# TangPrimer_no_jtag.net
KiCad netlist of a schematic drawn in EAGLE
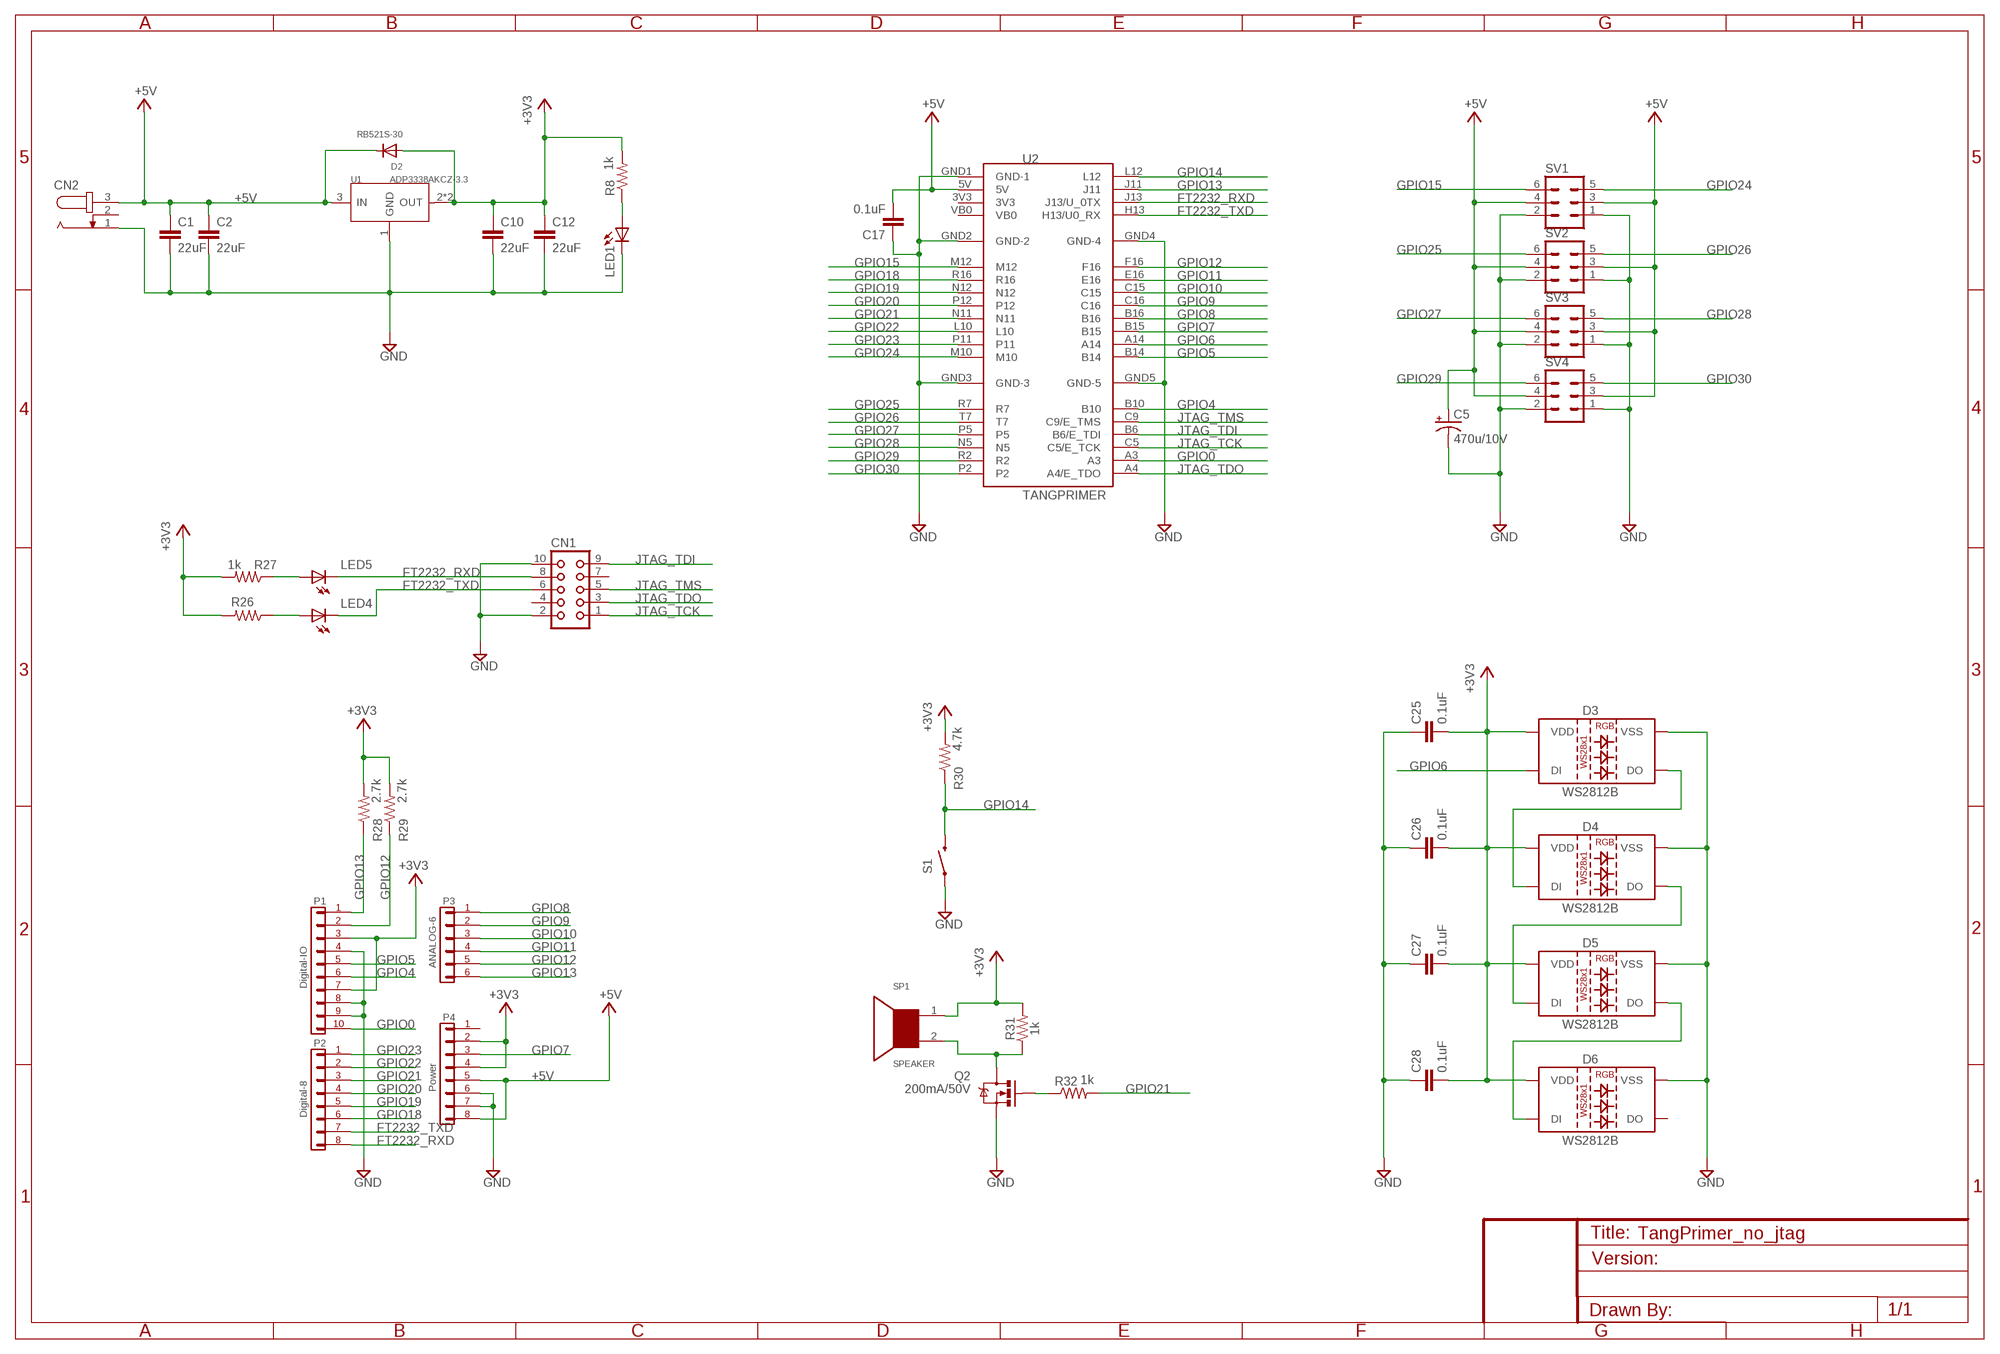
[diagram p0: schematic, sheet 1]

(export (version "E")
  (design (tool "Eeschema 10.0.6"))
  (components
    (comp (ref "C1")
      (value "22uF")
      (footprint "eagle-import:0603")
      (libsource (lib "eagle-import") (part "10UF-0603-6.3V-20%"))
    )
    (comp (ref "C2")
      (value "22uF")
      (footprint "eagle-import:0603")
      (libsource (lib "eagle-import") (part "10UF-0603-6.3V-20%"))
    )
    (comp (ref "C5")
      (value "470u/10V")
      (footprint "eagle-import:E2,5-7")
      (libsource (lib "eagle-import") (part "CPOL-USE2.5-7"))
    )
    (comp (ref "C10")
      (value "22uF")
      (footprint "eagle-import:0603")
      (libsource (lib "eagle-import") (part "10UF-0603-6.3V-20%"))
    )
    (comp (ref "C12")
      (value "22uF")
      (footprint "eagle-import:0603")
      (libsource (lib "eagle-import") (part "10UF-0603-6.3V-20%"))
    )
    (comp (ref "C17")
      (value "0.1uF")
      (footprint "eagle-import:0603")
      (libsource (lib "eagle-import") (part "0.1UF-0603-25V-5%"))
    )
    (comp (ref "C25")
      (value "0.1uF")
      (footprint "eagle-import:0603")
      (libsource (lib "eagle-import") (part "0.1UF-0603-25V-5%"))
    )
    (comp (ref "C26")
      (value "0.1uF")
      (footprint "eagle-import:0603")
      (libsource (lib "eagle-import") (part "0.1UF-0603-25V-5%"))
    )
    (comp (ref "C27")
      (value "0.1uF")
      (footprint "eagle-import:0603")
      (libsource (lib "eagle-import") (part "0.1UF-0603-25V-5%"))
    )
    (comp (ref "C28")
      (value "0.1uF")
      (footprint "eagle-import:0603")
      (libsource (lib "eagle-import") (part "0.1UF-0603-25V-5%"))
    )
    (comp (ref "CN1")
      (value "CON10")
      (footprint "eagle-import:CON10")
      (libsource (lib "eagle-import") (part "CON10"))
    )
    (comp (ref "CN2")
      (value "JACK-PLUG0")
      (footprint "eagle-import:SPC4077")
      (libsource (lib "eagle-import") (part "JACK-PLUG0"))
    )
    (comp (ref "D2")
      (value "RB521S-30")
      (footprint "eagle-import:SOD-523")
      (libsource (lib "eagle-import") (part "DIODESOD-523"))
    )
    (comp (ref "D3")
      (value "WS2812B")
      (footprint "eagle-import:WS2812_2020")
      (libsource (lib "eagle-import") (part "WS2812_2020"))
    )
    (comp (ref "D4")
      (value "WS2812B")
      (footprint "eagle-import:WS2812_2020")
      (libsource (lib "eagle-import") (part "WS2812_2020"))
    )
    (comp (ref "D5")
      (value "WS2812B")
      (footprint "eagle-import:WS2812_2020")
      (libsource (lib "eagle-import") (part "WS2812_2020"))
    )
    (comp (ref "D6")
      (value "WS2812B")
      (footprint "eagle-import:WS2812_2020")
      (libsource (lib "eagle-import") (part "WS2812_2020"))
    )
    (comp (ref "LED1")
      (value "LEDCHIP-LED0805")
      (footprint "eagle-import:CHIP-LED0805")
      (libsource (lib "eagle-import") (part "LEDCHIP-LED0805"))
    )
    (comp (ref "LED4")
      (value "LEDCHIP-LED0805")
      (footprint "eagle-import:CHIP-LED0805")
      (libsource (lib "eagle-import") (part "LEDCHIP-LED0805"))
    )
    (comp (ref "LED5")
      (value "LEDCHIP-LED0805")
      (footprint "eagle-import:CHIP-LED0805")
      (libsource (lib "eagle-import") (part "LEDCHIP-LED0805"))
    )
    (comp (ref "Q2")
      (value "200mA/50V")
      (footprint "eagle-import:SOT23-3")
      (libsource (lib "eagle-import") (part "MOSFET-NCHANNELBSS138"))
    )
    (comp (ref "R8")
      (value "1k")
      (footprint "eagle-import:0603")
      (libsource (lib "eagle-import") (part "RESISTOR0603"))
    )
    (comp (ref "R26")
      (value "1k")
      (footprint "eagle-import:0603")
      (libsource (lib "eagle-import") (part "RESISTOR0603"))
    )
    (comp (ref "R27")
      (value "1k")
      (footprint "eagle-import:0603")
      (libsource (lib "eagle-import") (part "RESISTOR0603"))
    )
    (comp (ref "R28")
      (value "2.7k")
      (footprint "eagle-import:0603")
      (libsource (lib "eagle-import") (part "RESISTOR0603"))
    )
    (comp (ref "R29")
      (value "2.7k")
      (footprint "eagle-import:0603")
      (libsource (lib "eagle-import") (part "RESISTOR0603"))
    )
    (comp (ref "R30")
      (value "4.7k")
      (footprint "eagle-import:0603")
      (libsource (lib "eagle-import") (part "RESISTOR0603"))
    )
    (comp (ref "R31")
      (value "1k")
      (footprint "eagle-import:0603")
      (libsource (lib "eagle-import") (part "RESISTOR0603"))
    )
    (comp (ref "R32")
      (value "1k")
      (footprint "eagle-import:0603")
      (libsource (lib "eagle-import") (part "RESISTOR0603"))
    )
    (comp (ref "S1")
      (value "SWITCH-MOMENTARY-2SMD-1101NE")
      (footprint "eagle-import:TACTILE-SWITCH-1101NE")
      (libsource (lib "eagle-import") (part "SWITCH-MOMENTARY-2SMD-1101NE"))
    )
    (comp (ref "S2")
      (value "TANGPRIMER_BASE")
      (footprint "eagle-import:TANGPRIMER_BASE")
      (libsource (lib "eagle-import") (part "TANGPRIMER_BASE"))
    )
    (comp (ref "SP1")
      (value "SPEAKER")
      (footprint "eagle-import:SPEAKER")
      (libsource (lib "eagle-import") (part "SPEAKER"))
    )
    (comp (ref "SV1")
      (value "MA03-2")
      (footprint "eagle-import:MA03-2")
      (libsource (lib "eagle-import") (part "MA03-2"))
    )
    (comp (ref "SV2")
      (value "MA03-2")
      (footprint "eagle-import:MA03-2")
      (libsource (lib "eagle-import") (part "MA03-2"))
    )
    (comp (ref "SV3")
      (value "MA03-2")
      (footprint "eagle-import:MA03-2")
      (libsource (lib "eagle-import") (part "MA03-2"))
    )
    (comp (ref "SV4")
      (value "MA03-2")
      (footprint "eagle-import:MA03-2")
      (libsource (lib "eagle-import") (part "MA03-2"))
    )
    (comp (ref "U1")
      (value "ADP3338AKCZ-3.3")
      (footprint "eagle-import:SOT-223")
      (fields (field (name "MPN") "CJT1117-3.3"))
      (libsource (lib "eagle-import") (part "PMIC-CJT1117-3.3(SOT223)"))
    )
    (comp (ref "U2")
      (value "TANGPRIMER")
      (footprint "eagle-import:TANGPRIMER")
      (libsource (lib "eagle-import") (part "TANGPRIMER"))
    )
  )
  (nets
    (net (code "1") (name "+3V3") (class "Default")
      (node (ref "C10") (pin "1") (pinfunction "1_1") (pintype "passive"))
      (node (ref "C12") (pin "1") (pinfunction "1_1") (pintype "passive"))
      (node (ref "C25") (pin "2") (pinfunction "2_2") (pintype "passive"))
      (node (ref "C26") (pin "2") (pinfunction "2_2") (pintype "passive"))
      (node (ref "C27") (pin "2") (pinfunction "2_2") (pintype "passive"))
      (node (ref "C28") (pin "2") (pinfunction "2_2") (pintype "passive"))
      (node (ref "D2") (pin "A") (pinfunction "A_A") (pintype "passive"))
      (node (ref "D3") (pin "4") (pinfunction "VDD_4") (pintype "bidirectional"))
      (node (ref "D4") (pin "4") (pinfunction "VDD_4") (pintype "bidirectional"))
      (node (ref "D5") (pin "4") (pinfunction "VDD_4") (pintype "bidirectional"))
      (node (ref "D6") (pin "4") (pinfunction "VDD_4") (pintype "bidirectional"))
      (node (ref "R26") (pin "2") (pinfunction "2_2") (pintype "passive"))
      (node (ref "R27") (pin "2") (pinfunction "2_2") (pintype "passive"))
      (node (ref "R28") (pin "2") (pinfunction "2_2") (pintype "passive"))
      (node (ref "R29") (pin "2") (pinfunction "2_2") (pintype "passive"))
      (node (ref "R30") (pin "2") (pinfunction "2_2") (pintype "passive"))
      (node (ref "R31") (pin "2") (pinfunction "2_2") (pintype "passive"))
      (node (ref "R8") (pin "2") (pinfunction "2_2") (pintype "passive"))
      (node (ref "S2") (pin "3V3-1") (pinfunction "3V3-1_3V3-1") (pintype "bidirectional"))
      (node (ref "S2") (pin "3V3-2") (pinfunction "3V3-2_3V3-2") (pintype "bidirectional"))
      (node (ref "S2") (pin "AREF") (pinfunction "AREF_AREF") (pintype "bidirectional"))
      (node (ref "S2") (pin "D11") (pinfunction "D11_D11") (pintype "bidirectional"))
      (node (ref "SP1") (pin "1") (pinfunction "1_1") (pintype "bidirectional"))
      (node (ref "U1") (pin "2") (pinfunction "OUT_2") (pintype "bidirectional"))
      (node (ref "U1") (pin "TER") (pinfunction "OUT_TER") (pintype "bidirectional"))
    )
    (net (code "2") (name "+5V") (class "Default")
      (node (ref "C1") (pin "1") (pinfunction "1_1") (pintype "passive"))
      (node (ref "C17") (pin "2") (pinfunction "2_2") (pintype "passive"))
      (node (ref "C2") (pin "1") (pinfunction "1_1") (pintype "passive"))
      (node (ref "C5") (pin "+") (pinfunction "+_+") (pintype "passive"))
      (node (ref "CN2") (pin "3") (pinfunction "3_3") (pintype "passive"))
      (node (ref "D2") (pin "K") (pinfunction "C_K") (pintype "passive"))
      (node (ref "S2") (pin "5V") (pinfunction "5V_5V") (pintype "bidirectional"))
      (node (ref "S2") (pin "VIN") (pinfunction "VIN_VIN") (pintype "bidirectional"))
      (node (ref "SV1") (pin "3") (pinfunction "3_3") (pintype "passive"))
      (node (ref "SV1") (pin "4") (pinfunction "4_4") (pintype "passive"))
      (node (ref "SV2") (pin "3") (pinfunction "3_3") (pintype "passive"))
      (node (ref "SV2") (pin "4") (pinfunction "4_4") (pintype "passive"))
      (node (ref "SV3") (pin "3") (pinfunction "3_3") (pintype "passive"))
      (node (ref "SV3") (pin "4") (pinfunction "4_4") (pintype "passive"))
      (node (ref "SV4") (pin "3") (pinfunction "3_3") (pintype "passive"))
      (node (ref "SV4") (pin "4") (pinfunction "4_4") (pintype "passive"))
      (node (ref "U1") (pin "3") (pinfunction "IN_3") (pintype "bidirectional"))
      (node (ref "U2") (pin "5V") (pinfunction "5V_5V") (pintype "passive"))
    )
    (net (code "3") (name "/FT2232_RXD") (class "Default")
      (node (ref "CN1") (pin "8") (pinfunction "8_8") (pintype "passive"))
      (node (ref "LED5") (pin "C") (pinfunction "C_C") (pintype "passive"))
      (node (ref "S2") (pin "RXD") (pinfunction "RX_RXD") (pintype "bidirectional"))
      (node (ref "U2") (pin "J13") (pinfunction "J13/U_0TX_J13") (pintype "passive"))
    )
    (net (code "4") (name "/FT2232_TXD") (class "Default")
      (node (ref "CN1") (pin "6") (pinfunction "6_6") (pintype "passive"))
      (node (ref "LED4") (pin "C") (pinfunction "C_C") (pintype "passive"))
      (node (ref "S2") (pin "TXD") (pinfunction "TX_TXD") (pintype "bidirectional"))
      (node (ref "U2") (pin "H13") (pinfunction "H13/U0_RX_H13") (pintype "passive"))
    )
    (net (code "5") (name "/GPIO0") (class "Default")
      (node (ref "S2") (pin "D8") (pinfunction "D8_D8") (pintype "bidirectional"))
      (node (ref "U2") (pin "A3") (pinfunction "A3_A3") (pintype "passive"))
    )
    (net (code "6") (name "/GPIO4") (class "Default")
      (node (ref "S2") (pin "D12") (pinfunction "D12_D12") (pintype "bidirectional"))
      (node (ref "U2") (pin "B10") (pinfunction "B10_B10") (pintype "passive"))
    )
    (net (code "7") (name "/GPIO5") (class "Default")
      (node (ref "S2") (pin "D13") (pinfunction "D13_D13") (pintype "bidirectional"))
      (node (ref "U2") (pin "B14") (pinfunction "B14_B14") (pintype "passive"))
    )
    (net (code "8") (name "/GPIO6") (class "Default")
      (node (ref "D3") (pin "3") (pinfunction "DI_3") (pintype "bidirectional"))
      (node (ref "U2") (pin "A14") (pinfunction "A14_A14") (pintype "passive"))
    )
    (net (code "9") (name "/GPIO7") (class "Default")
      (node (ref "S2") (pin "RESET") (pinfunction "RESET_RESET") (pintype "bidirectional"))
      (node (ref "U2") (pin "B15") (pinfunction "B15_B15") (pintype "passive"))
    )
    (net (code "10") (name "/GPIO8") (class "Default")
      (node (ref "S2") (pin "A0") (pinfunction "A0_A0") (pintype "bidirectional"))
      (node (ref "U2") (pin "B16") (pinfunction "B16_B16") (pintype "passive"))
    )
    (net (code "11") (name "/GPIO9") (class "Default")
      (node (ref "S2") (pin "A1") (pinfunction "A1_A1") (pintype "bidirectional"))
      (node (ref "U2") (pin "C16") (pinfunction "C16_C16") (pintype "passive"))
    )
    (net (code "12") (name "/GPIO10") (class "Default")
      (node (ref "S2") (pin "A2") (pinfunction "A2_A2") (pintype "bidirectional"))
      (node (ref "U2") (pin "C15") (pinfunction "C15_C15") (pintype "passive"))
    )
    (net (code "13") (name "/GPIO11") (class "Default")
      (node (ref "S2") (pin "A3") (pinfunction "A3_A3") (pintype "bidirectional"))
      (node (ref "U2") (pin "E16") (pinfunction "E16_E16") (pintype "passive"))
    )
    (net (code "14") (name "/GPIO12") (class "Default")
      (node (ref "R29") (pin "1") (pinfunction "1_1") (pintype "passive"))
      (node (ref "S2") (pin "A4") (pinfunction "A4_A4") (pintype "bidirectional"))
      (node (ref "S2") (pin "SDA") (pinfunction "SDA_SDA") (pintype "bidirectional"))
      (node (ref "U2") (pin "F16") (pinfunction "F16_F16") (pintype "passive"))
    )
    (net (code "15") (name "/GPIO13") (class "Default")
      (node (ref "R28") (pin "1") (pinfunction "1_1") (pintype "passive"))
      (node (ref "S2") (pin "A5") (pinfunction "A5_A5") (pintype "bidirectional"))
      (node (ref "S2") (pin "SCL") (pinfunction "SCL_SCL") (pintype "bidirectional"))
      (node (ref "U2") (pin "J11") (pinfunction "J11_J11") (pintype "passive"))
    )
    (net (code "16") (name "/GPIO14") (class "Default")
      (node (ref "R30") (pin "1") (pinfunction "1_1") (pintype "passive"))
      (node (ref "S1") (pin "2") (pinfunction "2_2") (pintype "passive"))
      (node (ref "U2") (pin "L12") (pinfunction "L12_L12") (pintype "passive"))
    )
    (net (code "17") (name "/GPIO15") (class "Default")
      (node (ref "SV1") (pin "6") (pinfunction "6_6") (pintype "passive"))
      (node (ref "U2") (pin "M12") (pinfunction "M12_M12") (pintype "passive"))
    )
    (net (code "18") (name "/GPIO18") (class "Default")
      (node (ref "S2") (pin "D2") (pinfunction "D2_D2") (pintype "bidirectional"))
      (node (ref "U2") (pin "R16") (pinfunction "R16_R16") (pintype "passive"))
    )
    (net (code "19") (name "/GPIO19") (class "Default")
      (node (ref "S2") (pin "D3") (pinfunction "D3_D3") (pintype "bidirectional"))
      (node (ref "U2") (pin "N12") (pinfunction "N12_N12") (pintype "passive"))
    )
    (net (code "20") (name "/GPIO20") (class "Default")
      (node (ref "S2") (pin "D4") (pinfunction "D4_D4") (pintype "bidirectional"))
      (node (ref "U2") (pin "P12") (pinfunction "P12_P12") (pintype "passive"))
    )
    (net (code "21") (name "/GPIO21") (class "Default")
      (node (ref "R32") (pin "2") (pinfunction "2_2") (pintype "passive"))
      (node (ref "S2") (pin "D5") (pinfunction "D5_D5") (pintype "bidirectional"))
      (node (ref "U2") (pin "N11") (pinfunction "N11_N11") (pintype "passive"))
    )
    (net (code "22") (name "/GPIO22") (class "Default")
      (node (ref "S2") (pin "D6") (pinfunction "D6_D6") (pintype "bidirectional"))
      (node (ref "U2") (pin "L10") (pinfunction "L10_L10") (pintype "passive"))
    )
    (net (code "23") (name "/GPIO23") (class "Default")
      (node (ref "S2") (pin "D7") (pinfunction "D7_D7") (pintype "bidirectional"))
      (node (ref "U2") (pin "P11") (pinfunction "P11_P11") (pintype "passive"))
    )
    (net (code "24") (name "/GPIO24") (class "Default")
      (node (ref "SV1") (pin "5") (pinfunction "5_5") (pintype "passive"))
      (node (ref "U2") (pin "M10") (pinfunction "M10_M10") (pintype "passive"))
    )
    (net (code "25") (name "/GPIO25") (class "Default")
      (node (ref "SV2") (pin "6") (pinfunction "6_6") (pintype "passive"))
      (node (ref "U2") (pin "R7") (pinfunction "R7_R7") (pintype "passive"))
    )
    (net (code "26") (name "/GPIO26") (class "Default")
      (node (ref "SV2") (pin "5") (pinfunction "5_5") (pintype "passive"))
      (node (ref "U2") (pin "T7") (pinfunction "T7_T7") (pintype "passive"))
    )
    (net (code "27") (name "/GPIO27") (class "Default")
      (node (ref "SV3") (pin "6") (pinfunction "6_6") (pintype "passive"))
      (node (ref "U2") (pin "P5") (pinfunction "P5_P5") (pintype "passive"))
    )
    (net (code "28") (name "/GPIO28") (class "Default")
      (node (ref "SV3") (pin "5") (pinfunction "5_5") (pintype "passive"))
      (node (ref "U2") (pin "N5") (pinfunction "N5_N5") (pintype "passive"))
    )
    (net (code "29") (name "/GPIO29") (class "Default")
      (node (ref "SV4") (pin "6") (pinfunction "6_6") (pintype "passive"))
      (node (ref "U2") (pin "R2") (pinfunction "R2_R2") (pintype "passive"))
    )
    (net (code "30") (name "/GPIO30") (class "Default")
      (node (ref "SV4") (pin "5") (pinfunction "5_5") (pintype "passive"))
      (node (ref "U2") (pin "P2") (pinfunction "P2_P2") (pintype "passive"))
    )
    (net (code "31") (name "/JTAG_TCK") (class "Default")
      (node (ref "CN1") (pin "1") (pinfunction "1_1") (pintype "passive"))
      (node (ref "U2") (pin "C5") (pinfunction "C5/E_TCK_C5") (pintype "passive"))
    )
    (net (code "32") (name "/JTAG_TDI") (class "Default")
      (node (ref "CN1") (pin "9") (pinfunction "9_9") (pintype "passive"))
      (node (ref "U2") (pin "B6") (pinfunction "B6/E_TDI_B6") (pintype "passive"))
    )
    (net (code "33") (name "/JTAG_TDO") (class "Default")
      (node (ref "CN1") (pin "3") (pinfunction "3_3") (pintype "passive"))
      (node (ref "U2") (pin "A4") (pinfunction "A4/E_TDO_A4") (pintype "passive"))
    )
    (net (code "34") (name "/JTAG_TMS") (class "Default")
      (node (ref "CN1") (pin "5") (pinfunction "5_5") (pintype "passive"))
      (node (ref "U2") (pin "C9") (pinfunction "C9/E_TMS_C9") (pintype "passive"))
    )
    (net (code "35") (name "GND") (class "Default")
      (node (ref "C1") (pin "2") (pinfunction "2_2") (pintype "passive"))
      (node (ref "C10") (pin "2") (pinfunction "2_2") (pintype "passive"))
      (node (ref "C12") (pin "2") (pinfunction "2_2") (pintype "passive"))
      (node (ref "C17") (pin "1") (pinfunction "1_1") (pintype "passive"))
      (node (ref "C2") (pin "2") (pinfunction "2_2") (pintype "passive"))
      (node (ref "C25") (pin "1") (pinfunction "1_1") (pintype "passive"))
      (node (ref "C26") (pin "1") (pinfunction "1_1") (pintype "passive"))
      (node (ref "C27") (pin "1") (pinfunction "1_1") (pintype "passive"))
      (node (ref "C28") (pin "1") (pinfunction "1_1") (pintype "passive"))
      (node (ref "C5") (pin "-") (pinfunction "-_-") (pintype "passive"))
      (node (ref "CN1") (pin "10") (pinfunction "10_10") (pintype "passive"))
      (node (ref "CN1") (pin "2") (pinfunction "2_2") (pintype "passive"))
      (node (ref "CN2") (pin "1") (pinfunction "1_1") (pintype "passive"))
      (node (ref "D3") (pin "2") (pinfunction "VSS_2") (pintype "bidirectional"))
      (node (ref "D4") (pin "2") (pinfunction "VSS_2") (pintype "bidirectional"))
      (node (ref "D5") (pin "2") (pinfunction "VSS_2") (pintype "bidirectional"))
      (node (ref "D6") (pin "2") (pinfunction "VSS_2") (pintype "bidirectional"))
      (node (ref "LED1") (pin "C") (pinfunction "C_C") (pintype "passive"))
      (node (ref "Q2") (pin "2") (pinfunction "S_2") (pintype "passive"))
      (node (ref "S1") (pin "1") (pinfunction "1_1") (pintype "passive"))
      (node (ref "S2") (pin "D10") (pinfunction "D10_D10") (pintype "bidirectional"))
      (node (ref "S2") (pin "D9") (pinfunction "D9_D9") (pintype "bidirectional"))
      (node (ref "S2") (pin "GND-1") (pinfunction "GND1_GND-1") (pintype "bidirectional"))
      (node (ref "S2") (pin "GND-2") (pinfunction "GND2_GND-2") (pintype "bidirectional"))
      (node (ref "S2") (pin "GND-3") (pinfunction "GND3_GND-3") (pintype "bidirectional"))
      (node (ref "SV1") (pin "1") (pinfunction "1_1") (pintype "passive"))
      (node (ref "SV1") (pin "2") (pinfunction "2_2") (pintype "passive"))
      (node (ref "SV2") (pin "1") (pinfunction "1_1") (pintype "passive"))
      (node (ref "SV2") (pin "2") (pinfunction "2_2") (pintype "passive"))
      (node (ref "SV3") (pin "1") (pinfunction "1_1") (pintype "passive"))
      (node (ref "SV3") (pin "2") (pinfunction "2_2") (pintype "passive"))
      (node (ref "SV4") (pin "1") (pinfunction "1_1") (pintype "passive"))
      (node (ref "SV4") (pin "2") (pinfunction "2_2") (pintype "passive"))
      (node (ref "U1") (pin "1") (pinfunction "GND_1") (pintype "bidirectional"))
      (node (ref "U2") (pin "GND1") (pinfunction "GND-1_GND1") (pintype "passive"))
      (node (ref "U2") (pin "GND2") (pinfunction "GND-2_GND2") (pintype "passive"))
      (node (ref "U2") (pin "GND3") (pinfunction "GND-3_GND3") (pintype "passive"))
      (node (ref "U2") (pin "GND4") (pinfunction "GND-4_GND4") (pintype "passive"))
      (node (ref "U2") (pin "GND5") (pinfunction "GND-5_GND5") (pintype "passive"))
    )
    (net (code "36") (name "Net-(D3-DO)") (class "Default")
      (node (ref "D3") (pin "1") (pinfunction "DO_1") (pintype "bidirectional"))
      (node (ref "D4") (pin "3") (pinfunction "DI_3") (pintype "bidirectional"))
    )
    (net (code "37") (name "Net-(D4-DO)") (class "Default")
      (node (ref "D4") (pin "1") (pinfunction "DO_1") (pintype "bidirectional"))
      (node (ref "D5") (pin "3") (pinfunction "DI_3") (pintype "bidirectional"))
    )
    (net (code "38") (name "Net-(D5-DO)") (class "Default")
      (node (ref "D5") (pin "1") (pinfunction "DO_1") (pintype "bidirectional"))
      (node (ref "D6") (pin "3") (pinfunction "DI_3") (pintype "bidirectional"))
    )
    (net (code "39") (name "Net-(LED1-PadA)") (class "Default")
      (node (ref "LED1") (pin "A") (pinfunction "A_A") (pintype "passive"))
      (node (ref "R8") (pin "1") (pinfunction "1_1") (pintype "passive"))
    )
    (net (code "40") (name "Net-(LED4-PadA)") (class "Default")
      (node (ref "LED4") (pin "A") (pinfunction "A_A") (pintype "passive"))
      (node (ref "R26") (pin "1") (pinfunction "1_1") (pintype "passive"))
    )
    (net (code "41") (name "Net-(LED5-PadA)") (class "Default")
      (node (ref "LED5") (pin "A") (pinfunction "A_A") (pintype "passive"))
      (node (ref "R27") (pin "1") (pinfunction "1_1") (pintype "passive"))
    )
    (net (code "42") (name "Net-(Q2-D)") (class "Default")
      (node (ref "Q2") (pin "3") (pinfunction "D_3") (pintype "passive"))
      (node (ref "R31") (pin "1") (pinfunction "1_1") (pintype "passive"))
      (node (ref "SP1") (pin "2") (pinfunction "2_2") (pintype "bidirectional"))
    )
    (net (code "43") (name "Net-(Q2-G)") (class "Default")
      (node (ref "Q2") (pin "1") (pinfunction "G_1") (pintype "passive"))
      (node (ref "R32") (pin "1") (pinfunction "1_1") (pintype "passive"))
    )
    (net (code "44") (name "unconnected-(CN1-Pad4)") (class "Default")
      (node (ref "CN1") (pin "4") (pinfunction "4_4") (pintype "passive"))
    )
    (net (code "45") (name "unconnected-(CN1-Pad7)") (class "Default")
      (node (ref "CN1") (pin "7") (pinfunction "7_7") (pintype "passive"))
    )
    (net (code "46") (name "unconnected-(CN2-Pad2)") (class "Default")
      (node (ref "CN2") (pin "2") (pinfunction "2_2") (pintype "passive"))
    )
    (net (code "47") (name "unconnected-(D6-DO-Pad1)") (class "Default")
      (node (ref "D6") (pin "1") (pinfunction "DO_1") (pintype "bidirectional"))
    )
    (net (code "48") (name "unconnected-(S2-PadRESERVED)") (class "Default")
      (node (ref "S2") (pin "RESERVED") (pinfunction "RESERVED_RESERVED") (pintype "bidirectional"))
    )
    (net (code "49") (name "unconnected-(U2-Pad3V3)") (class "Default")
      (node (ref "U2") (pin "3V3") (pinfunction "3V3_3V3") (pintype "passive"))
    )
    (net (code "50") (name "unconnected-(U2-PadVB0)") (class "Default")
      (node (ref "U2") (pin "VB0") (pinfunction "VB0_VB0") (pintype "passive"))
    )
  )
)
